# CH32V203C6T6-R0.net
KiCad netlist of a schematic drawn in Altium Designer
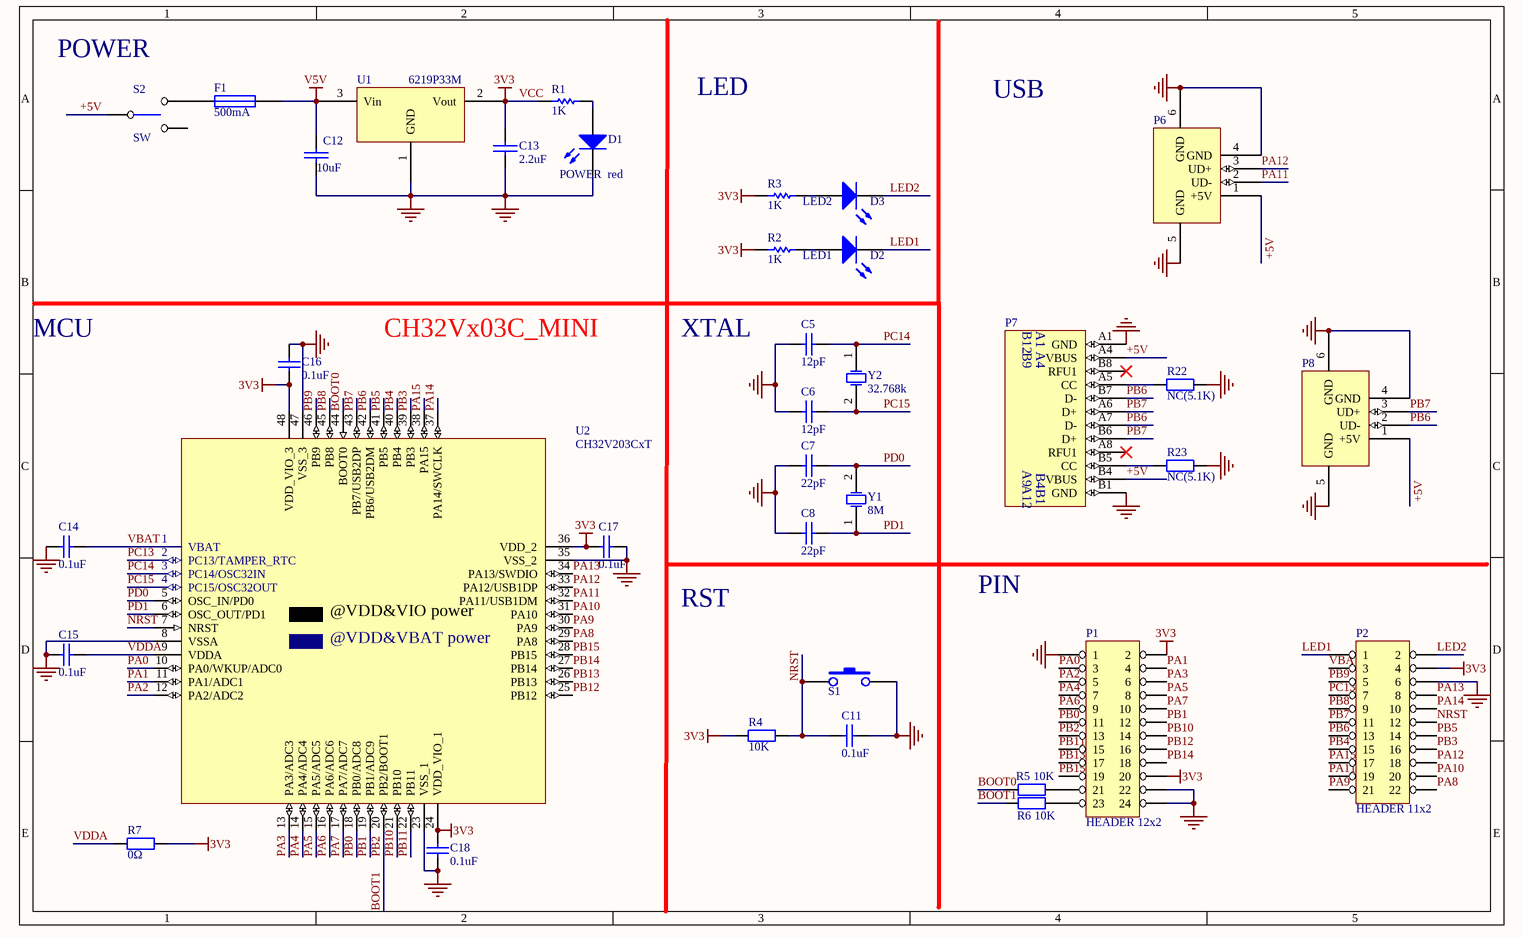
[diagram p0: CH32V203C6T6-R0.SchDoc]

(export (version "E")
  (design (tool "Eeschema 10.0.6"))
  (components
    (comp (ref "C5")
      (value "12pF")
      (footprint "0603_C")
      (description "Capacitor")
      (fields (field (name "PUBLISHER") "Altium Limited"))
      (libsource (lib "*") (part "Cap"))
    )
    (comp (ref "C6")
      (value "12pF")
      (footprint "0603_C")
      (description "Capacitor")
      (fields (field (name "PUBLISHER") "Altium Limited"))
      (libsource (lib "*") (part "Cap"))
    )
    (comp (ref "C7")
      (value "22pF")
      (footprint "0603_C")
      (description "Capacitor")
      (fields (field (name "PUBLISHER") "Altium Limited"))
      (libsource (lib "*") (part "Cap"))
    )
    (comp (ref "C8")
      (value "22pF")
      (footprint "0603_C")
      (description "Capacitor")
      (fields (field (name "PUBLISHER") "Altium Limited"))
      (libsource (lib "*") (part "Cap"))
    )
    (comp (ref "C11")
      (value "0.1uF")
      (footprint "0603_C")
      (description "Capacitor")
      (fields (field (name "PUBLISHER") "Altium Limited"))
      (libsource (lib "*") (part "Cap"))
    )
    (comp (ref "C12")
      (value "10uF")
      (footprint "3216_C")
      (description "Capacitor")
      (libsource (lib "*") (part "CAP"))
    )
    (comp (ref "C13")
      (value "2.2uF")
      (footprint "0603_C")
      (description "Capacitor")
      (libsource (lib "*") (part "CAP"))
    )
    (comp (ref "C14")
      (value "0.1uF")
      (footprint "0603_C")
      (description "Capacitor")
      (fields (field (name "PUBLISHER") "Altium Limited"))
      (libsource (lib "*") (part "Cap"))
    )
    (comp (ref "C15")
      (value "0.1uF")
      (footprint "0603_C")
      (description "Capacitor")
      (fields (field (name "PUBLISHER") "Altium Limited"))
      (libsource (lib "*") (part "Cap"))
    )
    (comp (ref "C16")
      (value "0.1uF")
      (footprint "0603_C")
      (description "Capacitor")
      (fields (field (name "PUBLISHER") "Altium Limited"))
      (libsource (lib "*") (part "Cap"))
    )
    (comp (ref "C17")
      (value "0.1uF")
      (footprint "0603_C")
      (description "Capacitor")
      (fields (field (name "PUBLISHER") "Altium Limited"))
      (libsource (lib "*") (part "Cap"))
    )
    (comp (ref "C18")
      (value "0.1uF")
      (footprint "0603_C")
      (description "Capacitor")
      (fields (field (name "PUBLISHER") "Altium Limited"))
      (libsource (lib "*") (part "Cap"))
    )
    (comp (ref "D1")
      (value "POWER  red")
      (footprint "0603+")
      (description "Typical INFRARED GaAs LED")
      (fields (field (name "PUBLISHER") "Altium Limited"))
      (libsource (lib "*") (part "LED0"))
    )
    (comp (ref "D2")
      (value "LED1")
      (footprint "0603+")
      (description "Typical INFRARED GaAs LED")
      (fields (field (name "PUBLISHER") "Altium Limited"))
      (libsource (lib "*") (part "LED0"))
    )
    (comp (ref "D3")
      (value "LED2")
      (footprint "0603+")
      (description "Typical INFRARED GaAs LED")
      (fields (field (name "PUBLISHER") "Altium Limited"))
      (libsource (lib "*") (part "LED0"))
    )
    (comp (ref "F1")
      (value "500mA")
      (footprint "0603")
      (description "Fuse")
      (libsource (lib "*") (part "FUSE1"))
    )
    (comp (ref "P1")
      (value "HEADER 12x2")
      (footprint "MYPCB:IDC24-2.54MM")
      (description "Header, 12-Pin, Dual row")
      (libsource (lib "wch_sch_others") (part "HEADER 12x2"))
    )
    (comp (ref "P2")
      (value "HEADER 11x2")
      (footprint "MYPCB:IDC22-2.54MM")
      (description "Header, 11-Pin, Dual row")
      (libsource (lib "wch_sch_others") (part "HEADER 11x2"))
    )
    (comp (ref "P6")
      (value "USB_A")
      (footprint "USBAF")
      (description "USB Port")
      (libsource (lib "*") (part "USB"))
    )
    (comp (ref "P7")
      (value "TYPE-C")
      (footprint "TYPE-C-Receptacle-2.0")
      (libsource (lib "*") (part "TYPE-C1"))
    )
    (comp (ref "P8")
      (value "USB_A")
      (footprint "USBAF")
      (description "USB Port")
      (libsource (lib "*") (part "USB"))
    )
    (comp (ref "R1")
      (value "1K")
      (footprint "0603")
      (description "Semiconductor Resistor")
      (fields (field (name "PUBLISHER") "Altium Limited"))
      (libsource (lib "*") (part "Res Semi"))
    )
    (comp (ref "R2")
      (value "1K")
      (footprint "0603")
      (description "Semiconductor Resistor")
      (fields (field (name "PUBLISHER") "Altium Limited"))
      (libsource (lib "*") (part "Res Semi"))
    )
    (comp (ref "R3")
      (value "1K")
      (footprint "0603")
      (description "Semiconductor Resistor")
      (fields (field (name "PUBLISHER") "Altium Limited"))
      (libsource (lib "*") (part "Res Semi"))
    )
    (comp (ref "R4")
      (value "10K")
      (footprint "0603")
      (description "Resistor")
      (fields (field (name "PUBLISHER") "Altium Limited"))
      (libsource (lib "*") (part "Res2"))
    )
    (comp (ref "R5")
      (value "10K")
      (footprint "0603")
      (description "Resistor")
      (fields (field (name "PUBLISHER") "Altium Limited"))
      (libsource (lib "") (part "Res2_1"))
    )
    (comp (ref "R6")
      (value "10K")
      (footprint "0603")
      (description "Resistor")
      (fields (field (name "PUBLISHER") "Altium Limited"))
      (libsource (lib "") (part "Res2_1"))
    )
    (comp (ref "R7")
      (value "0Ω")
      (footprint "0603")
      (description "Resistor")
      (fields (field (name "PUBLISHER") "Altium Limited"))
      (libsource (lib "*") (part "Res2"))
    )
    (comp (ref "R22")
      (value "NC(5.1K)")
      (footprint "0603")
      (description "Resistor")
      (libsource (lib "Miscellaneous Devices") (part "Res2"))
    )
    (comp (ref "R23")
      (value "NC(5.1K)")
      (footprint "0603")
      (description "Resistor")
      (libsource (lib "Miscellaneous Devices") (part "Res2"))
    )
    (comp (ref "S1") (value "KEY") (footprint "贴片按键") (libsource (lib "*") (part "KEY")))
    (comp (ref "S2") (value "SW") (footprint "KEY2") (libsource (lib "*") (part "SW")))
    (comp (ref "U1")
      (value "6219P33M")
      (footprint "SOT-23")
      (libsource (lib "wch_sch_others") (part "6219P33M"))
    )
    (comp (ref "U2")
      (value "CH32V203CxT")
      (footprint "LQFP48")
      (description "RISC-V LMD-MCU, 144MHz, 2*USB FS, CAN")
      (libsource (lib "CHXXX") (part "CH32V203CxT"))
    )
    (comp (ref "Y1")
      (value "8M")
      (footprint "XT_AT49")
      (description "Crystal Oscillator")
      (fields (field (name "PUBLISHER") "Altium Limited"))
      (libsource (lib "*") (part "XTAL"))
    )
    (comp (ref "Y2")
      (value "32.768k")
      (footprint "FC-135")
      (description "Crystal Oscillator")
      (fields (field (name "PUBLISHER") "Altium Limited"))
      (libsource (lib "*") (part "XTAL"))
    )
  )
  (nets
    (net (code "1") (name "/+5V") (class "Default")
      (node (ref "P6") (pin "1") (pinfunction "+5V_1") (pintype "power_in"))
      (node (ref "P7") (pin "A4") (pinfunction "VBUS_A4") (pintype "bidirectional"))
      (node (ref "P7") (pin "B4") (pinfunction "VBUS_B4") (pintype "bidirectional"))
      (node (ref "P8") (pin "1") (pinfunction "+5V_1") (pintype "power_in"))
      (node (ref "S2") (pin "1") (pinfunction "1_1") (pintype "passive"))
    )
    (net (code "3") (name "/BOOT0") (class "Default")
      (node (ref "R5") (pin "1") (pinfunction "1_1") (pintype "passive"))
      (node (ref "U2") (pin "44") (pinfunction "BOOT0_44") (pintype "input"))
    )
    (net (code "4") (name "/BOOT1") (class "Default")
      (node (ref "P1") (pin "13") (pinfunction "13_13") (pintype "passive"))
      (node (ref "R6") (pin "1") (pinfunction "1_1") (pintype "passive"))
      (node (ref "U2") (pin "20") (pinfunction "PB2/BOOT1_20") (pintype "bidirectional"))
    )
    (net (code "5") (name "/LED1") (class "Default")
      (node (ref "D2") (pin "2") (pinfunction "K_2") (pintype "passive"))
      (node (ref "P2") (pin "1") (pinfunction "1_1") (pintype "passive"))
    )
    (net (code "6") (name "/LED2") (class "Default")
      (node (ref "D3") (pin "2") (pinfunction "K_2") (pintype "passive"))
      (node (ref "P2") (pin "2") (pinfunction "2_2") (pintype "passive"))
    )
    (net (code "7") (name "/NRST") (class "Default")
      (node (ref "C11") (pin "2") (pinfunction "2_2") (pintype "passive"))
      (node (ref "P2") (pin "12") (pinfunction "12_12") (pintype "passive"))
      (node (ref "R4") (pin "1") (pinfunction "1_1") (pintype "passive"))
      (node (ref "S1") (pin "1") (pinfunction "1_1") (pintype "passive"))
      (node (ref "U2") (pin "7") (pinfunction "NRST_7") (pintype "input"))
    )
    (net (code "8") (name "/PA0") (class "Default")
      (node (ref "P1") (pin "3") (pinfunction "3_3") (pintype "passive"))
      (node (ref "U2") (pin "10") (pinfunction "PA0/WKUP/ADC0_10") (pintype "bidirectional"))
    )
    (net (code "9") (name "/PA1") (class "Default")
      (node (ref "P1") (pin "4") (pinfunction "4_4") (pintype "passive"))
      (node (ref "U2") (pin "11") (pinfunction "PA1/ADC1_11") (pintype "bidirectional"))
    )
    (net (code "10") (name "/PA2") (class "Default")
      (node (ref "P1") (pin "5") (pinfunction "5_5") (pintype "passive"))
      (node (ref "U2") (pin "12") (pinfunction "PA2/ADC2_12") (pintype "bidirectional"))
    )
    (net (code "11") (name "/PA3") (class "Default")
      (node (ref "P1") (pin "6") (pinfunction "6_6") (pintype "passive"))
      (node (ref "U2") (pin "13") (pinfunction "PA3/ADC3_13") (pintype "bidirectional"))
    )
    (net (code "12") (name "/PA4") (class "Default")
      (node (ref "P1") (pin "7") (pinfunction "7_7") (pintype "passive"))
      (node (ref "U2") (pin "14") (pinfunction "PA4/ADC4_14") (pintype "bidirectional"))
    )
    (net (code "13") (name "/PA5") (class "Default")
      (node (ref "P1") (pin "8") (pinfunction "8_8") (pintype "passive"))
      (node (ref "U2") (pin "15") (pinfunction "PA5/ADC5_15") (pintype "bidirectional"))
    )
    (net (code "14") (name "/PA6") (class "Default")
      (node (ref "P1") (pin "9") (pinfunction "9_9") (pintype "passive"))
      (node (ref "U2") (pin "16") (pinfunction "PA6/ADC6_16") (pintype "bidirectional"))
    )
    (net (code "15") (name "/PA7") (class "Default")
      (node (ref "P1") (pin "10") (pinfunction "10_10") (pintype "passive"))
      (node (ref "U2") (pin "17") (pinfunction "PA7/ADC7_17") (pintype "bidirectional"))
    )
    (net (code "16") (name "/PA8") (class "Default")
      (node (ref "P2") (pin "22") (pinfunction "22_22") (pintype "passive"))
      (node (ref "U2") (pin "29") (pinfunction "PA8_29") (pintype "bidirectional"))
    )
    (net (code "17") (name "/PA9") (class "Default")
      (node (ref "P2") (pin "21") (pinfunction "21_21") (pintype "passive"))
      (node (ref "U2") (pin "30") (pinfunction "PA9_30") (pintype "bidirectional"))
    )
    (net (code "18") (name "/PA10") (class "Default")
      (node (ref "P2") (pin "20") (pinfunction "20_20") (pintype "passive"))
      (node (ref "U2") (pin "31") (pinfunction "PA10_31") (pintype "bidirectional"))
    )
    (net (code "19") (name "/PA11") (class "Default")
      (node (ref "P2") (pin "19") (pinfunction "19_19") (pintype "passive"))
      (node (ref "P6") (pin "2") (pinfunction "UD-_2") (pintype "bidirectional"))
      (node (ref "U2") (pin "32") (pinfunction "PA11/USB1DM_32") (pintype "bidirectional"))
    )
    (net (code "20") (name "/PA12") (class "Default")
      (node (ref "P2") (pin "18") (pinfunction "18_18") (pintype "passive"))
      (node (ref "P6") (pin "3") (pinfunction "UD+_3") (pintype "bidirectional"))
      (node (ref "U2") (pin "33") (pinfunction "PA12/USB1DP_33") (pintype "bidirectional"))
    )
    (net (code "21") (name "/PA13") (class "Default")
      (node (ref "P2") (pin "8") (pinfunction "8_8") (pintype "passive"))
      (node (ref "U2") (pin "34") (pinfunction "PA13/SWDIO_34") (pintype "bidirectional"))
    )
    (net (code "22") (name "/PA14") (class "Default")
      (node (ref "P2") (pin "10") (pinfunction "10_10") (pintype "passive"))
      (node (ref "U2") (pin "37") (pinfunction "PA14/SWCLK_37") (pintype "bidirectional"))
    )
    (net (code "23") (name "/PA15") (class "Default")
      (node (ref "P2") (pin "17") (pinfunction "17_17") (pintype "passive"))
      (node (ref "U2") (pin "38") (pinfunction "PA15_38") (pintype "bidirectional"))
    )
    (net (code "24") (name "/PB0") (class "Default")
      (node (ref "P1") (pin "11") (pinfunction "11_11") (pintype "passive"))
      (node (ref "U2") (pin "18") (pinfunction "PB0/ADC8_18") (pintype "bidirectional"))
    )
    (net (code "25") (name "/PB1") (class "Default")
      (node (ref "P1") (pin "12") (pinfunction "12_12") (pintype "passive"))
      (node (ref "U2") (pin "19") (pinfunction "PB1/ADC9_19") (pintype "bidirectional"))
    )
    (net (code "26") (name "/PB3") (class "Default")
      (node (ref "P2") (pin "16") (pinfunction "16_16") (pintype "passive"))
      (node (ref "U2") (pin "39") (pinfunction "PB3_39") (pintype "bidirectional"))
    )
    (net (code "27") (name "/PB4") (class "Default")
      (node (ref "P2") (pin "15") (pinfunction "15_15") (pintype "passive"))
      (node (ref "U2") (pin "40") (pinfunction "PB4_40") (pintype "bidirectional"))
    )
    (net (code "28") (name "/PB5") (class "Default")
      (node (ref "P2") (pin "14") (pinfunction "14_14") (pintype "passive"))
      (node (ref "U2") (pin "41") (pinfunction "PB5_41") (pintype "bidirectional"))
    )
    (net (code "29") (name "/PB6") (class "Default")
      (node (ref "P2") (pin "13") (pinfunction "13_13") (pintype "passive"))
      (node (ref "P7") (pin "A7") (pinfunction "D-_A7") (pintype "bidirectional"))
      (node (ref "P7") (pin "B7") (pinfunction "D-_B7") (pintype "bidirectional"))
      (node (ref "P8") (pin "2") (pinfunction "UD-_2") (pintype "bidirectional"))
      (node (ref "U2") (pin "42") (pinfunction "PB6/USB2DM_42") (pintype "bidirectional"))
    )
    (net (code "30") (name "/PB7") (class "Default")
      (node (ref "P2") (pin "11") (pinfunction "11_11") (pintype "passive"))
      (node (ref "P7") (pin "A6") (pinfunction "D+_A6") (pintype "bidirectional"))
      (node (ref "P7") (pin "B6") (pinfunction "D+_B6") (pintype "bidirectional"))
      (node (ref "P8") (pin "3") (pinfunction "UD+_3") (pintype "bidirectional"))
      (node (ref "U2") (pin "43") (pinfunction "PB7/USB2DP_43") (pintype "bidirectional"))
    )
    (net (code "31") (name "/PB8") (class "Default")
      (node (ref "P2") (pin "9") (pinfunction "9_9") (pintype "passive"))
      (node (ref "U2") (pin "45") (pinfunction "PB8_45") (pintype "bidirectional"))
    )
    (net (code "32") (name "/PB9") (class "Default")
      (node (ref "P2") (pin "5") (pinfunction "5_5") (pintype "passive"))
      (node (ref "U2") (pin "46") (pinfunction "PB9_46") (pintype "bidirectional"))
    )
    (net (code "33") (name "/PB10") (class "Default")
      (node (ref "P1") (pin "14") (pinfunction "14_14") (pintype "passive"))
      (node (ref "U2") (pin "21") (pinfunction "PB10_21") (pintype "bidirectional"))
    )
    (net (code "34") (name "/PB11") (class "Default")
      (node (ref "P1") (pin "15") (pinfunction "15_15") (pintype "passive"))
      (node (ref "U2") (pin "22") (pinfunction "PB11_22") (pintype "bidirectional"))
    )
    (net (code "35") (name "/PB12") (class "Default")
      (node (ref "P1") (pin "16") (pinfunction "16_16") (pintype "passive"))
      (node (ref "U2") (pin "25") (pinfunction "PB12_25") (pintype "bidirectional"))
    )
    (net (code "36") (name "/PB13") (class "Default")
      (node (ref "P1") (pin "17") (pinfunction "17_17") (pintype "passive"))
      (node (ref "U2") (pin "26") (pinfunction "PB13_26") (pintype "bidirectional"))
    )
    (net (code "37") (name "/PB14") (class "Default")
      (node (ref "P1") (pin "18") (pinfunction "18_18") (pintype "passive"))
      (node (ref "U2") (pin "27") (pinfunction "PB14_27") (pintype "bidirectional"))
    )
    (net (code "38") (name "/PB15") (class "Default")
      (node (ref "P1") (pin "19") (pinfunction "19_19") (pintype "passive"))
      (node (ref "U2") (pin "28") (pinfunction "PB15_28") (pintype "bidirectional"))
    )
    (net (code "39") (name "/PC13") (class "Default")
      (node (ref "P2") (pin "7") (pinfunction "7_7") (pintype "passive"))
      (node (ref "U2") (pin "2") (pinfunction "PC13/TAMPER_RTC_2") (pintype "bidirectional"))
    )
    (net (code "40") (name "/PC14") (class "Default")
      (node (ref "C5") (pin "1") (pinfunction "1_1") (pintype "passive"))
      (node (ref "U2") (pin "3") (pinfunction "PC14/OSC32IN_3") (pintype "bidirectional"))
      (node (ref "Y2") (pin "1") (pinfunction "OSC1_1") (pintype "passive"))
    )
    (net (code "41") (name "/PC15") (class "Default")
      (node (ref "C6") (pin "1") (pinfunction "1_1") (pintype "passive"))
      (node (ref "U2") (pin "4") (pinfunction "PC15/OSC32OUT_4") (pintype "bidirectional"))
      (node (ref "Y2") (pin "2") (pinfunction "OSC2_2") (pintype "passive"))
    )
    (net (code "42") (name "/PD0") (class "Default")
      (node (ref "C7") (pin "2") (pinfunction "2_2") (pintype "passive"))
      (node (ref "U2") (pin "5") (pinfunction "OSC_IN/PD0_5") (pintype "bidirectional"))
      (node (ref "Y1") (pin "2") (pinfunction "OSC2_2") (pintype "passive"))
    )
    (net (code "43") (name "/PD1") (class "Default")
      (node (ref "C8") (pin "2") (pinfunction "2_2") (pintype "passive"))
      (node (ref "U2") (pin "6") (pinfunction "OSC_OUT/PD1_6") (pintype "bidirectional"))
      (node (ref "Y1") (pin "1") (pinfunction "OSC1_1") (pintype "passive"))
    )
    (net (code "44") (name "/VBAT") (class "Default")
      (node (ref "C14") (pin "1") (pinfunction "1_1") (pintype "passive"))
      (node (ref "P2") (pin "3") (pinfunction "3_3") (pintype "passive"))
      (node (ref "U2") (pin "1") (pinfunction "VBAT_1") (pintype "power_in"))
    )
    (net (code "45") (name "/VDDA") (class "Default")
      (node (ref "C15") (pin "1") (pinfunction "1_1") (pintype "passive"))
      (node (ref "R7") (pin "2") (pinfunction "2_2") (pintype "passive"))
      (node (ref "U2") (pin "9") (pinfunction "VDDA_9") (pintype "power_in"))
    )
    (net (code "46") (name "3V3") (class "Default")
      (node (ref "C13") (pin "1") (pinfunction "1_1") (pintype "passive"))
      (node (ref "C16") (pin "2") (pinfunction "2_2") (pintype "passive"))
      (node (ref "C17") (pin "2") (pinfunction "2_2") (pintype "passive"))
      (node (ref "C18") (pin "2") (pinfunction "2_2") (pintype "passive"))
      (node (ref "P1") (pin "2") (pinfunction "2_2") (pintype "passive"))
      (node (ref "P1") (pin "20") (pinfunction "20_20") (pintype "passive"))
      (node (ref "P2") (pin "4") (pinfunction "4_4") (pintype "passive"))
      (node (ref "R1") (pin "2") (pinfunction "2_2") (pintype "passive"))
      (node (ref "R2") (pin "1") (pinfunction "1_1") (pintype "passive"))
      (node (ref "R3") (pin "1") (pinfunction "1_1") (pintype "passive"))
      (node (ref "R4") (pin "2") (pinfunction "2_2") (pintype "passive"))
      (node (ref "R7") (pin "1") (pinfunction "1_1") (pintype "passive"))
      (node (ref "U1") (pin "2") (pinfunction "Vout_2") (pintype "passive"))
      (node (ref "U2") (pin "24") (pinfunction "VDD_VIO_1_24") (pintype "power_in"))
      (node (ref "U2") (pin "36") (pinfunction "VDD_2_36") (pintype "power_in"))
      (node (ref "U2") (pin "48") (pinfunction "VDD_VIO_3_48") (pintype "power_in"))
    )
    (net (code "47") (name "GND") (class "Default")
      (node (ref "C11") (pin "1") (pinfunction "1_1") (pintype "passive"))
      (node (ref "C12") (pin "2") (pinfunction "2_2") (pintype "passive"))
      (node (ref "C13") (pin "2") (pinfunction "2_2") (pintype "passive"))
      (node (ref "C14") (pin "2") (pinfunction "2_2") (pintype "passive"))
      (node (ref "C15") (pin "2") (pinfunction "2_2") (pintype "passive"))
      (node (ref "C16") (pin "1") (pinfunction "1_1") (pintype "passive"))
      (node (ref "C17") (pin "1") (pinfunction "1_1") (pintype "passive"))
      (node (ref "C18") (pin "1") (pinfunction "1_1") (pintype "passive"))
      (node (ref "C5") (pin "2") (pinfunction "2_2") (pintype "passive"))
      (node (ref "C6") (pin "2") (pinfunction "2_2") (pintype "passive"))
      (node (ref "C7") (pin "1") (pinfunction "1_1") (pintype "passive"))
      (node (ref "C8") (pin "1") (pinfunction "1_1") (pintype "passive"))
      (node (ref "D1") (pin "2") (pinfunction "K_2") (pintype "passive"))
      (node (ref "P1") (pin "1") (pinfunction "1_1") (pintype "passive"))
      (node (ref "P1") (pin "22") (pinfunction "22_22") (pintype "passive"))
      (node (ref "P1") (pin "24") (pinfunction "24_24") (pintype "passive"))
      (node (ref "P2") (pin "6") (pinfunction "6_6") (pintype "passive"))
      (node (ref "P6") (pin "4") (pinfunction "GND_4") (pintype "power_in"))
      (node (ref "P6") (pin "5") (pinfunction "GND_5") (pintype "power_in"))
      (node (ref "P6") (pin "6") (pinfunction "GND_6") (pintype "power_in"))
      (node (ref "P7") (pin "A1") (pinfunction "GND_A1") (pintype "bidirectional"))
      (node (ref "P7") (pin "B1") (pinfunction "GND_B1") (pintype "bidirectional"))
      (node (ref "P8") (pin "4") (pinfunction "GND_4") (pintype "power_in"))
      (node (ref "P8") (pin "5") (pinfunction "GND_5") (pintype "power_in"))
      (node (ref "P8") (pin "6") (pinfunction "GND_6") (pintype "power_in"))
      (node (ref "R22") (pin "2") (pinfunction "2_2") (pintype "passive"))
      (node (ref "R23") (pin "2") (pinfunction "2_2") (pintype "passive"))
      (node (ref "S1") (pin "2") (pinfunction "2_2") (pintype "passive"))
      (node (ref "U1") (pin "1") (pinfunction "GND_1") (pintype "passive"))
      (node (ref "U2") (pin "23") (pinfunction "VSS_1_23") (pintype "power_in"))
      (node (ref "U2") (pin "35") (pinfunction "VSS_2_35") (pintype "power_in"))
      (node (ref "U2") (pin "47") (pinfunction "VSS_3_47") (pintype "power_in"))
      (node (ref "U2") (pin "8") (pinfunction "VSSA_8") (pintype "power_in"))
    )
    (net (code "48") (name "Net-(D1-A)") (class "Default")
      (node (ref "D1") (pin "1") (pinfunction "A_1") (pintype "passive"))
      (node (ref "R1") (pin "1") (pinfunction "1_1") (pintype "passive"))
    )
    (net (code "49") (name "Net-(D2-A)") (class "Default")
      (node (ref "D2") (pin "1") (pinfunction "A_1") (pintype "passive"))
      (node (ref "R2") (pin "2") (pinfunction "2_2") (pintype "passive"))
    )
    (net (code "50") (name "Net-(D3-A)") (class "Default")
      (node (ref "D3") (pin "1") (pinfunction "A_1") (pintype "passive"))
      (node (ref "R3") (pin "2") (pinfunction "2_2") (pintype "passive"))
    )
    (net (code "51") (name "Net-(F1-Pad1)") (class "Default")
      (node (ref "F1") (pin "1") (pinfunction "1_1") (pintype "passive"))
      (node (ref "S2") (pin "3") (pinfunction "3_3") (pintype "passive"))
    )
    (net (code "52") (name "Net-(P1-Pad21)") (class "Default")
      (node (ref "P1") (pin "21") (pinfunction "21_21") (pintype "passive"))
      (node (ref "R5") (pin "2") (pinfunction "2_2") (pintype "passive"))
    )
    (net (code "53") (name "Net-(P1-Pad23)") (class "Default")
      (node (ref "P1") (pin "23") (pinfunction "23_23") (pintype "passive"))
      (node (ref "R6") (pin "2") (pinfunction "2_2") (pintype "passive"))
    )
    (net (code "54") (name "Net-(P7-CC-PadA5)") (class "Default")
      (node (ref "P7") (pin "A5") (pinfunction "CC_A5") (pintype "bidirectional"))
      (node (ref "R22") (pin "1") (pinfunction "1_1") (pintype "passive"))
    )
    (net (code "55") (name "Net-(P7-CC-PadB5)") (class "Default")
      (node (ref "P7") (pin "B5") (pinfunction "CC_B5") (pintype "bidirectional"))
      (node (ref "R23") (pin "1") (pinfunction "1_1") (pintype "passive"))
    )
    (net (code "56") (name "V5V") (class "Default")
      (node (ref "C12") (pin "1") (pinfunction "1_1") (pintype "passive"))
      (node (ref "F1") (pin "2") (pinfunction "2_2") (pintype "passive"))
      (node (ref "U1") (pin "3") (pinfunction "Vin_3") (pintype "passive"))
    )
    (net (code "57") (name "unconnected-(P7-RFU1-PadA8)") (class "Default")
      (node (ref "P7") (pin "A8") (pinfunction "RFU1_A8") (pintype "bidirectional+no_connect"))
    )
    (net (code "58") (name "unconnected-(P7-RFU1-PadB8)") (class "Default")
      (node (ref "P7") (pin "B8") (pinfunction "RFU1_B8") (pintype "bidirectional+no_connect"))
    )
    (net (code "59") (name "unconnected-(S2-Pad2)") (class "Default")
      (node (ref "S2") (pin "2") (pinfunction "2_2") (pintype "passive"))
    )
  )
)
